# ATM90E3x-DB.net
KiCad netlist of a schematic drawn in Altium Designer
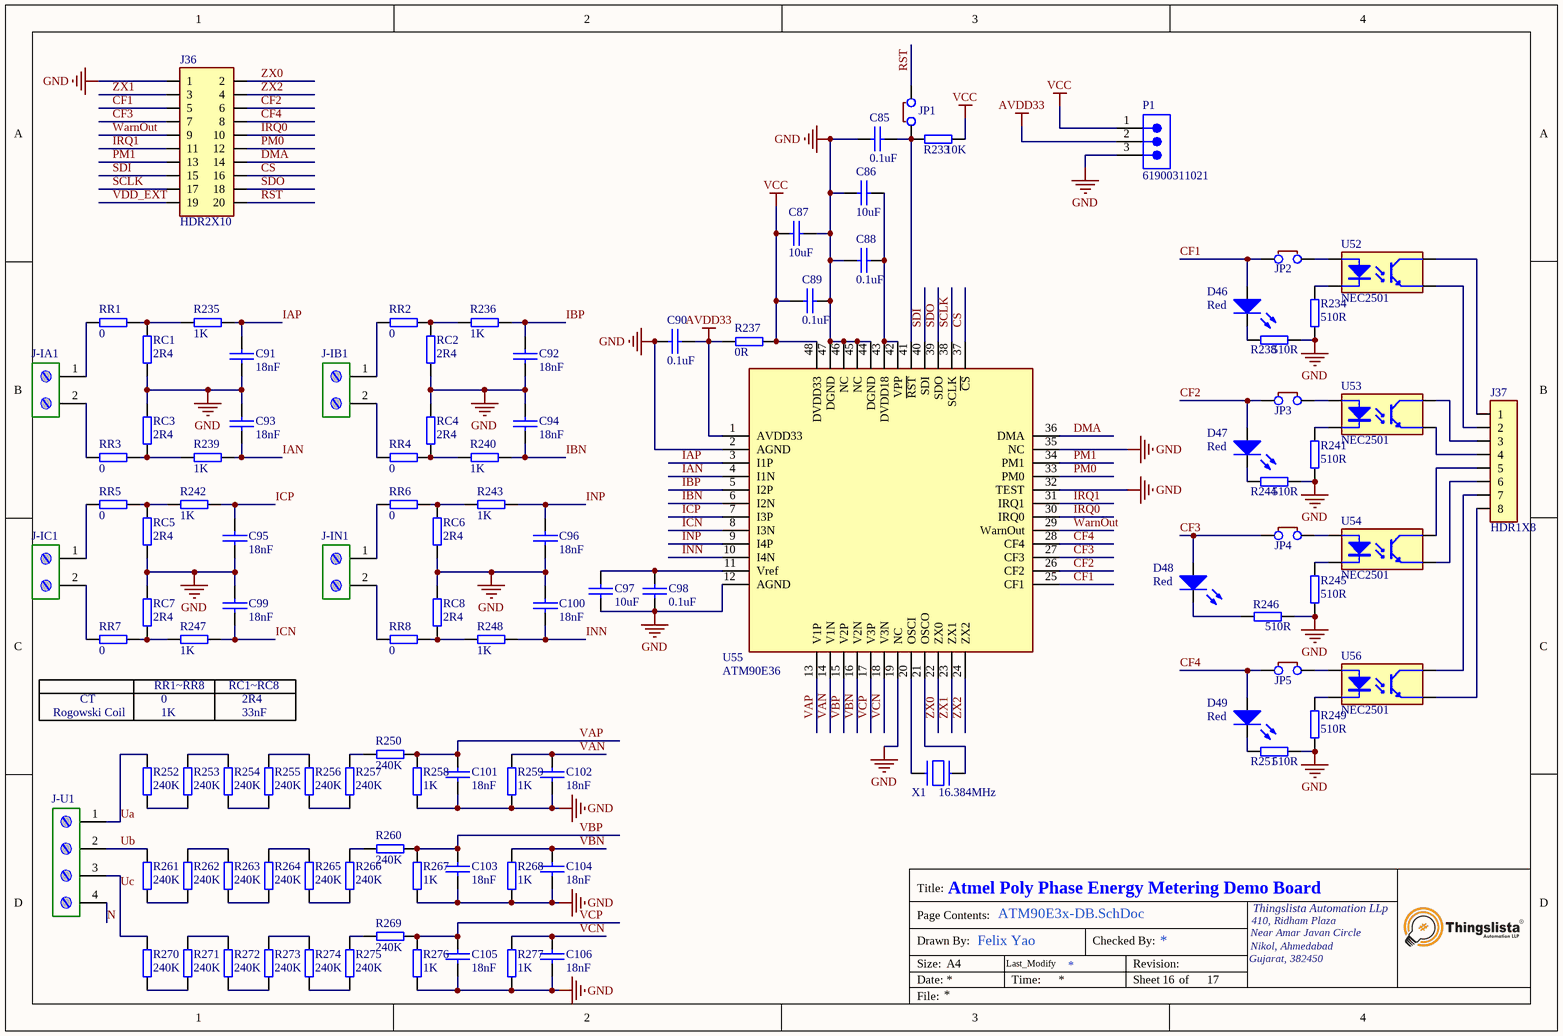
[diagram p0: ATM90E3x-DB.SchDoc]

(export (version "E")
  (design (tool "Eeschema 10.0.6"))
  (components
    (comp (ref "C85") (value "0.1uF") (footprint "C0603") (libsource (lib "SchLib(AD10)") (part "CAP")))
    (comp (ref "C86") (value "10uF") (footprint "C0805") (libsource (lib "SchLib(AD10)") (part "CAP")))
    (comp (ref "C87") (value "10uF") (footprint "C0805") (libsource (lib "SchLib(AD10)") (part "CAP")))
    (comp (ref "C88") (value "0.1uF") (footprint "C0603") (libsource (lib "SchLib(AD10)") (part "CAP")))
    (comp (ref "C89") (value "0.1uF") (footprint "C0603") (libsource (lib "SchLib(AD10)") (part "CAP")))
    (comp (ref "C90") (value "0.1uF") (footprint "C0603") (libsource (lib "SchLib(AD10)") (part "CAP")))
    (comp (ref "C91") (value "18nF") (footprint "C0805") (libsource (lib "SchLib(AD10)") (part "CAP")))
    (comp (ref "C92") (value "18nF") (footprint "C0805") (libsource (lib "SchLib(AD10)") (part "CAP")))
    (comp (ref "C93") (value "18nF") (footprint "C0805") (libsource (lib "SchLib(AD10)") (part "CAP")))
    (comp (ref "C94") (value "18nF") (footprint "C0805") (libsource (lib "SchLib(AD10)") (part "CAP")))
    (comp (ref "C95") (value "18nF") (footprint "C0805") (libsource (lib "SchLib(AD10)") (part "CAP")))
    (comp (ref "C96") (value "18nF") (footprint "C0805") (libsource (lib "SchLib(AD10)") (part "CAP")))
    (comp (ref "C97") (value "10uF") (footprint "C0805") (libsource (lib "SchLib(AD10)") (part "CAP")))
    (comp (ref "C98") (value "0.1uF") (footprint "C0603") (libsource (lib "SchLib(AD10)") (part "CAP")))
    (comp (ref "C99") (value "18nF") (footprint "C0805") (libsource (lib "SchLib(AD10)") (part "CAP")))
    (comp (ref "C100") (value "18nF") (footprint "C0805") (libsource (lib "SchLib(AD10)") (part "CAP")))
    (comp (ref "C101") (value "18nF") (footprint "C0805") (libsource (lib "SchLib(AD10)") (part "CAP")))
    (comp (ref "C102") (value "18nF") (footprint "C0805") (libsource (lib "SchLib(AD10)") (part "CAP")))
    (comp (ref "C103") (value "18nF") (footprint "C0805") (libsource (lib "SchLib(AD10)") (part "CAP")))
    (comp (ref "C104") (value "18nF") (footprint "C0805") (libsource (lib "SchLib(AD10)") (part "CAP")))
    (comp (ref "C105") (value "18nF") (footprint "C0805") (libsource (lib "SchLib(AD10)") (part "CAP")))
    (comp (ref "C106") (value "18nF") (footprint "C0805") (libsource (lib "SchLib(AD10)") (part "CAP")))
    (comp (ref "D46") (value "Red") (footprint "LED-0805R") (libsource (lib "SchLib(AD10)") (part "LED")))
    (comp (ref "D47") (value "Red") (footprint "LED-0805R") (libsource (lib "SchLib(AD10)") (part "LED")))
    (comp (ref "D48") (value "Red") (footprint "LED-0805R") (libsource (lib "SchLib(AD10)") (part "LED")))
    (comp (ref "D49") (value "Red") (footprint "LED-0805R") (libsource (lib "SchLib(AD10)") (part "LED")))
    (comp (ref "J-IA1")
      (value "~")
      (footprint "TE-1776119-2")
      (libsource (lib "SchLib(AD10)") (part "Terminal-Screw-2"))
    )
    (comp (ref "J-IB1")
      (value "~")
      (footprint "TE-1776119-2")
      (libsource (lib "SchLib(AD10)") (part "Terminal-Screw-2"))
    )
    (comp (ref "J-IC1")
      (value "~")
      (footprint "TE-1776119-2")
      (libsource (lib "SchLib(AD10)") (part "Terminal-Screw-2"))
    )
    (comp (ref "J-IN1")
      (value "~")
      (footprint "TE-1776119-2")
      (libsource (lib "SchLib(AD10)") (part "Terminal-Screw-2"))
    )
    (comp (ref "J-U1")
      (value "~")
      (footprint "TE-282843-4")
      (libsource (lib "SchLib(AD10)") (part "Terminal-Screw-4"))
    )
    (comp (ref "J36")
      (value "HDR2X10")
      (footprint "HDR2X10")
      (libsource (lib "SchLib(AD10)") (part "HDR2X10"))
    )
    (comp (ref "J37") (value "HDR1X8") (footprint "HDR1X8") (libsource (lib "SchLib(AD10)") (part "HDR1X8")))
    (comp (ref "JP1") (value "JMP") (footprint "JMP") (libsource (lib "SchLib(AD10)") (part "JMP")))
    (comp (ref "JP2") (value "JMP") (footprint "JMP") (libsource (lib "SchLib(AD10)") (part "JMP")))
    (comp (ref "JP3") (value "JMP") (footprint "JMP") (libsource (lib "SchLib(AD10)") (part "JMP")))
    (comp (ref "JP4") (value "JMP") (footprint "JMP") (libsource (lib "SchLib(AD10)") (part "JMP")))
    (comp (ref "JP5") (value "JMP") (footprint "JMP") (libsource (lib "SchLib(AD10)") (part "JMP")))
    (comp (ref "P1")
      (value "61900311021")
      (footprint "61900311021")
      (libsource (lib "Altium Content Vault") (part "Header_Male_1R_03P"))
    )
    (comp (ref "R233") (value "10K") (footprint "R0603") (libsource (lib "SchLib(AD10)") (part "RES")))
    (comp (ref "R234") (value "510R") (footprint "R0805") (libsource (lib "SchLib(AD10)") (part "RES")))
    (comp (ref "R235") (value "1K") (footprint "R0805") (libsource (lib "SchLib(AD10)") (part "RES")))
    (comp (ref "R236") (value "1K") (footprint "R0805") (libsource (lib "SchLib(AD10)") (part "RES")))
    (comp (ref "R237") (value "0R") (footprint "R0603") (libsource (lib "SchLib(AD10)") (part "RES")))
    (comp (ref "R238") (value "510R") (footprint "R0805") (libsource (lib "SchLib(AD10)") (part "RES")))
    (comp (ref "R239") (value "1K") (footprint "R0805") (libsource (lib "SchLib(AD10)") (part "RES")))
    (comp (ref "R240") (value "1K") (footprint "R0805") (libsource (lib "SchLib(AD10)") (part "RES")))
    (comp (ref "R241") (value "510R") (footprint "R0805") (libsource (lib "SchLib(AD10)") (part "RES")))
    (comp (ref "R242") (value "1K") (footprint "R0805") (libsource (lib "SchLib(AD10)") (part "RES")))
    (comp (ref "R243") (value "1K") (footprint "R0805") (libsource (lib "SchLib(AD10)") (part "RES")))
    (comp (ref "R244") (value "510R") (footprint "R0805") (libsource (lib "SchLib(AD10)") (part "RES")))
    (comp (ref "R245") (value "510R") (footprint "R0805") (libsource (lib "SchLib(AD10)") (part "RES")))
    (comp (ref "R246") (value "510R") (footprint "R0805") (libsource (lib "SchLib(AD10)") (part "RES")))
    (comp (ref "R247") (value "1K") (footprint "R0805") (libsource (lib "SchLib(AD10)") (part "RES")))
    (comp (ref "R248") (value "1K") (footprint "R0805") (libsource (lib "SchLib(AD10)") (part "RES")))
    (comp (ref "R249") (value "510R") (footprint "R0805") (libsource (lib "SchLib(AD10)") (part "RES")))
    (comp (ref "R250") (value "240K") (footprint "R1206") (libsource (lib "SchLib(AD10)") (part "RES")))
    (comp (ref "R251") (value "510R") (footprint "R0805") (libsource (lib "SchLib(AD10)") (part "RES")))
    (comp (ref "R252") (value "240K") (footprint "R1206") (libsource (lib "SchLib(AD10)") (part "RES")))
    (comp (ref "R253") (value "240K") (footprint "R1206") (libsource (lib "SchLib(AD10)") (part "RES")))
    (comp (ref "R254") (value "240K") (footprint "R1206") (libsource (lib "SchLib(AD10)") (part "RES")))
    (comp (ref "R255") (value "240K") (footprint "R1206") (libsource (lib "SchLib(AD10)") (part "RES")))
    (comp (ref "R256") (value "240K") (footprint "R1206") (libsource (lib "SchLib(AD10)") (part "RES")))
    (comp (ref "R257") (value "240K") (footprint "R1206") (libsource (lib "SchLib(AD10)") (part "RES")))
    (comp (ref "R258") (value "1K") (footprint "R0805") (libsource (lib "SchLib(AD10)") (part "RES")))
    (comp (ref "R259") (value "1K") (footprint "R0805") (libsource (lib "SchLib(AD10)") (part "RES")))
    (comp (ref "R260") (value "240K") (footprint "R1206") (libsource (lib "SchLib(AD10)") (part "RES")))
    (comp (ref "R261") (value "240K") (footprint "R1206") (libsource (lib "SchLib(AD10)") (part "RES")))
    (comp (ref "R262") (value "240K") (footprint "R1206") (libsource (lib "SchLib(AD10)") (part "RES")))
    (comp (ref "R263") (value "240K") (footprint "R1206") (libsource (lib "SchLib(AD10)") (part "RES")))
    (comp (ref "R264") (value "240K") (footprint "R1206") (libsource (lib "SchLib(AD10)") (part "RES")))
    (comp (ref "R265") (value "240K") (footprint "R1206") (libsource (lib "SchLib(AD10)") (part "RES")))
    (comp (ref "R266") (value "240K") (footprint "R1206") (libsource (lib "SchLib(AD10)") (part "RES")))
    (comp (ref "R267") (value "1K") (footprint "R0805") (libsource (lib "SchLib(AD10)") (part "RES")))
    (comp (ref "R268") (value "1K") (footprint "R0805") (libsource (lib "SchLib(AD10)") (part "RES")))
    (comp (ref "R269") (value "240K") (footprint "R1206") (libsource (lib "SchLib(AD10)") (part "RES")))
    (comp (ref "R270") (value "240K") (footprint "R1206") (libsource (lib "SchLib(AD10)") (part "RES")))
    (comp (ref "R271") (value "240K") (footprint "R1206") (libsource (lib "SchLib(AD10)") (part "RES")))
    (comp (ref "R272") (value "240K") (footprint "R1206") (libsource (lib "SchLib(AD10)") (part "RES")))
    (comp (ref "R273") (value "240K") (footprint "R1206") (libsource (lib "SchLib(AD10)") (part "RES")))
    (comp (ref "R274") (value "240K") (footprint "R1206") (libsource (lib "SchLib(AD10)") (part "RES")))
    (comp (ref "R275") (value "240K") (footprint "R1206") (libsource (lib "SchLib(AD10)") (part "RES")))
    (comp (ref "R276") (value "1K") (footprint "R0805") (libsource (lib "SchLib(AD10)") (part "RES")))
    (comp (ref "R277") (value "1K") (footprint "R0805") (libsource (lib "SchLib(AD10)") (part "RES")))
    (comp (ref "RC1") (value "2R4") (footprint "R0805") (libsource (lib "SchLib(AD10)") (part "RES")))
    (comp (ref "RC2") (value "2R4") (footprint "R0805") (libsource (lib "SchLib(AD10)") (part "RES")))
    (comp (ref "RC3") (value "2R4") (footprint "R0805") (libsource (lib "SchLib(AD10)") (part "RES")))
    (comp (ref "RC4") (value "2R4") (footprint "R0805") (libsource (lib "SchLib(AD10)") (part "RES")))
    (comp (ref "RC5") (value "2R4") (footprint "R0805") (libsource (lib "SchLib(AD10)") (part "RES")))
    (comp (ref "RC6") (value "2R4") (footprint "R0805") (libsource (lib "SchLib(AD10)") (part "RES")))
    (comp (ref "RC7") (value "2R4") (footprint "R0805") (libsource (lib "SchLib(AD10)") (part "RES")))
    (comp (ref "RC8") (value "2R4") (footprint "R0805") (libsource (lib "SchLib(AD10)") (part "RES")))
    (comp (ref "RR1") (value "0") (footprint "R0805") (libsource (lib "SchLib(AD10)") (part "RES")))
    (comp (ref "RR2") (value "0") (footprint "R0805") (libsource (lib "SchLib(AD10)") (part "RES")))
    (comp (ref "RR3") (value "0") (footprint "R0805") (libsource (lib "SchLib(AD10)") (part "RES")))
    (comp (ref "RR4") (value "0") (footprint "R0805") (libsource (lib "SchLib(AD10)") (part "RES")))
    (comp (ref "RR5") (value "0") (footprint "R0805") (libsource (lib "SchLib(AD10)") (part "RES")))
    (comp (ref "RR6") (value "0") (footprint "R0805") (libsource (lib "SchLib(AD10)") (part "RES")))
    (comp (ref "RR7") (value "0") (footprint "R0805") (libsource (lib "SchLib(AD10)") (part "RES")))
    (comp (ref "RR8") (value "0") (footprint "R0805") (libsource (lib "SchLib(AD10)") (part "RES")))
    (comp (ref "U52")
      (value "NEC2501")
      (footprint "PS2501L-1")
      (libsource (lib "SchLib(AD10)") (part "NEC2501"))
    )
    (comp (ref "U53")
      (value "NEC2501")
      (footprint "PS2501L-1")
      (libsource (lib "SchLib(AD10)") (part "NEC2501"))
    )
    (comp (ref "U54")
      (value "NEC2501")
      (footprint "PS2501L-1")
      (libsource (lib "SchLib(AD10)") (part "NEC2501"))
    )
    (comp (ref "U55")
      (value "ATM90E36")
      (footprint "TQFP-48(7x7)")
      (description "ATM90E3X")
      (libsource (lib "SchLib(AD10)") (part "ATM90E3X"))
    )
    (comp (ref "U56")
      (value "NEC2501")
      (footprint "PS2501L-1")
      (libsource (lib "SchLib(AD10)") (part "NEC2501"))
    )
    (comp (ref "X1")
      (value "16.384MHz")
      (footprint "XTAL-MIX-49")
      (libsource (lib "SchLib(AD10)") (part "XTAL-T"))
    )
  )
  (nets
    (net (code "1") (name "/CF1") (class "Default")
      (node (ref "D46") (pin "A") (pinfunction "A_A") (pintype "passive"))
      (node (ref "J36") (pin "5") (pinfunction "5_5") (pintype "passive"))
      (node (ref "JP2") (pin "1") (pinfunction "1_1") (pintype "passive"))
      (node (ref "U55") (pin "25") (pinfunction "CF1_25") (pintype "passive"))
    )
    (net (code "2") (name "/CF2") (class "Default")
      (node (ref "D47") (pin "A") (pinfunction "A_A") (pintype "passive"))
      (node (ref "J36") (pin "6") (pinfunction "6_6") (pintype "passive"))
      (node (ref "JP3") (pin "1") (pinfunction "1_1") (pintype "passive"))
      (node (ref "U55") (pin "26") (pinfunction "CF2_26") (pintype "passive"))
    )
    (net (code "3") (name "/CF3") (class "Default")
      (node (ref "D48") (pin "A") (pinfunction "A_A") (pintype "passive"))
      (node (ref "J36") (pin "7") (pinfunction "7_7") (pintype "passive"))
      (node (ref "JP4") (pin "1") (pinfunction "1_1") (pintype "passive"))
      (node (ref "U55") (pin "27") (pinfunction "CF3_27") (pintype "passive"))
    )
    (net (code "4") (name "/CF4") (class "Default")
      (node (ref "D49") (pin "A") (pinfunction "A_A") (pintype "passive"))
      (node (ref "J36") (pin "8") (pinfunction "8_8") (pintype "passive"))
      (node (ref "JP5") (pin "1") (pinfunction "1_1") (pintype "passive"))
      (node (ref "U55") (pin "28") (pinfunction "CF4_28") (pintype "passive"))
    )
    (net (code "5") (name "/CS") (class "Default")
      (node (ref "J36") (pin "16") (pinfunction "16_16") (pintype "passive"))
      (node (ref "U55") (pin "37") (pinfunction "~{CS}_37") (pintype "passive"))
    )
    (net (code "6") (name "/DMA") (class "Default")
      (node (ref "J36") (pin "14") (pinfunction "14_14") (pintype "passive"))
      (node (ref "U55") (pin "36") (pinfunction "DMA_36") (pintype "passive"))
    )
    (net (code "7") (name "/IAN") (class "Default")
      (node (ref "C93") (pin "1") (pintype "passive"))
      (node (ref "R239") (pin "1") (pinfunction "1_1") (pintype "passive"))
      (node (ref "U55") (pin "4") (pinfunction "I1N_4") (pintype "passive"))
    )
    (net (code "8") (name "/IAP") (class "Default")
      (node (ref "C91") (pin "2") (pintype "passive"))
      (node (ref "R235") (pin "1") (pinfunction "1_1") (pintype "passive"))
      (node (ref "U55") (pin "3") (pinfunction "I1P_3") (pintype "passive"))
    )
    (net (code "9") (name "/IBN") (class "Default")
      (node (ref "C94") (pin "2") (pintype "passive"))
      (node (ref "R240") (pin "2") (pinfunction "2_2") (pintype "passive"))
      (node (ref "U55") (pin "6") (pinfunction "I2N_6") (pintype "passive"))
    )
    (net (code "10") (name "/IBP") (class "Default")
      (node (ref "C92") (pin "1") (pintype "passive"))
      (node (ref "R236") (pin "2") (pinfunction "2_2") (pintype "passive"))
      (node (ref "U55") (pin "5") (pinfunction "I2P_5") (pintype "passive"))
    )
    (net (code "11") (name "/ICN") (class "Default")
      (node (ref "C99") (pin "2") (pintype "passive"))
      (node (ref "R247") (pin "2") (pinfunction "2_2") (pintype "passive"))
      (node (ref "U55") (pin "8") (pinfunction "I3N_8") (pintype "passive"))
    )
    (net (code "12") (name "/ICP") (class "Default")
      (node (ref "C95") (pin "1") (pintype "passive"))
      (node (ref "R242") (pin "2") (pinfunction "2_2") (pintype "passive"))
      (node (ref "U55") (pin "7") (pinfunction "I3P_7") (pintype "passive"))
    )
    (net (code "13") (name "/INN") (class "Default")
      (node (ref "C100") (pin "2") (pintype "passive"))
      (node (ref "R248") (pin "2") (pinfunction "2_2") (pintype "passive"))
      (node (ref "U55") (pin "10") (pinfunction "I4N_10") (pintype "passive"))
    )
    (net (code "14") (name "/INP") (class "Default")
      (node (ref "C96") (pin "1") (pintype "passive"))
      (node (ref "R243") (pin "2") (pinfunction "2_2") (pintype "passive"))
      (node (ref "U55") (pin "9") (pinfunction "I4P_9") (pintype "passive"))
    )
    (net (code "15") (name "/IRQ0") (class "Default")
      (node (ref "J36") (pin "10") (pinfunction "10_10") (pintype "passive"))
      (node (ref "U55") (pin "30") (pinfunction "IRQ0_30") (pintype "passive"))
    )
    (net (code "16") (name "/IRQ1") (class "Default")
      (node (ref "J36") (pin "11") (pinfunction "11_11") (pintype "passive"))
      (node (ref "U55") (pin "31") (pinfunction "IRQ1_31") (pintype "passive"))
    )
    (net (code "17") (name "/N") (class "Default")
      (node (ref "J-U1") (pin "4") (pinfunction "4_4") (pintype "passive"))
    )
    (net (code "18") (name "/PM0") (class "Default")
      (node (ref "J36") (pin "12") (pinfunction "12_12") (pintype "passive"))
      (node (ref "U55") (pin "33") (pinfunction "PM0_33") (pintype "passive"))
    )
    (net (code "19") (name "/PM1") (class "Default")
      (node (ref "J36") (pin "13") (pinfunction "13_13") (pintype "passive"))
      (node (ref "U55") (pin "34") (pinfunction "PM1_34") (pintype "passive"))
    )
    (net (code "20") (name "/RST") (class "Default")
      (node (ref "J36") (pin "20") (pinfunction "20_20") (pintype "passive"))
      (node (ref "JP1") (pin "2") (pinfunction "2_2") (pintype "passive"))
    )
    (net (code "21") (name "/SCLK") (class "Default")
      (node (ref "J36") (pin "17") (pinfunction "17_17") (pintype "passive"))
      (node (ref "U55") (pin "38") (pinfunction "SCLK_38") (pintype "passive"))
    )
    (net (code "22") (name "/SDI") (class "Default")
      (node (ref "J36") (pin "15") (pinfunction "15_15") (pintype "passive"))
      (node (ref "U55") (pin "40") (pinfunction "SDI_40") (pintype "passive"))
    )
    (net (code "23") (name "/SDO") (class "Default")
      (node (ref "J36") (pin "18") (pinfunction "18_18") (pintype "passive"))
      (node (ref "U55") (pin "39") (pinfunction "SDO_39") (pintype "passive"))
    )
    (net (code "24") (name "/Ua") (class "Default")
      (node (ref "J-U1") (pin "1") (pinfunction "1_1") (pintype "passive"))
      (node (ref "R252") (pin "1") (pinfunction "1_1") (pintype "passive"))
    )
    (net (code "25") (name "/Ub") (class "Default")
      (node (ref "J-U1") (pin "2") (pinfunction "2_2") (pintype "passive"))
      (node (ref "R261") (pin "2") (pinfunction "2_2") (pintype "passive"))
    )
    (net (code "26") (name "/Uc") (class "Default")
      (node (ref "J-U1") (pin "3") (pinfunction "3_3") (pintype "passive"))
      (node (ref "R270") (pin "2") (pinfunction "2_2") (pintype "passive"))
    )
    (net (code "27") (name "/VAN") (class "Default")
      (node (ref "C102") (pin "2") (pintype "passive"))
      (node (ref "R259") (pin "2") (pinfunction "2_2") (pintype "passive"))
      (node (ref "U55") (pin "14") (pinfunction "V1N_14") (pintype "passive"))
    )
    (net (code "28") (name "/VAP") (class "Default")
      (node (ref "C101") (pin "2") (pintype "passive"))
      (node (ref "R250") (pin "2") (pinfunction "2_2") (pintype "passive"))
      (node (ref "R258") (pin "2") (pinfunction "2_2") (pintype "passive"))
      (node (ref "U55") (pin "13") (pinfunction "V1P_13") (pintype "passive"))
    )
    (net (code "29") (name "/VBN") (class "Default")
      (node (ref "C104") (pin "2") (pintype "passive"))
      (node (ref "R268") (pin "2") (pinfunction "2_2") (pintype "passive"))
      (node (ref "U55") (pin "16") (pinfunction "V2N_16") (pintype "passive"))
    )
    (net (code "30") (name "/VBP") (class "Default")
      (node (ref "C103") (pin "2") (pintype "passive"))
      (node (ref "R260") (pin "1") (pinfunction "1_1") (pintype "passive"))
      (node (ref "R267") (pin "2") (pinfunction "2_2") (pintype "passive"))
      (node (ref "U55") (pin "15") (pinfunction "V2P_15") (pintype "passive"))
    )
    (net (code "31") (name "/VCN") (class "Default")
      (node (ref "C106") (pin "2") (pintype "passive"))
      (node (ref "R277") (pin "2") (pinfunction "2_2") (pintype "passive"))
      (node (ref "U55") (pin "18") (pinfunction "V3N_18") (pintype "passive"))
    )
    (net (code "32") (name "/VCP") (class "Default")
      (node (ref "C105") (pin "2") (pintype "passive"))
      (node (ref "R269") (pin "1") (pinfunction "1_1") (pintype "passive"))
      (node (ref "R276") (pin "2") (pinfunction "2_2") (pintype "passive"))
      (node (ref "U55") (pin "17") (pinfunction "V3P_17") (pintype "passive"))
    )
    (net (code "33") (name "/VDD_EXT") (class "Default")
      (node (ref "J36") (pin "19") (pinfunction "19_19") (pintype "passive"))
    )
    (net (code "34") (name "/WarnOut") (class "Default")
      (node (ref "J36") (pin "9") (pinfunction "9_9") (pintype "passive"))
      (node (ref "U55") (pin "29") (pinfunction "WarnOut_29") (pintype "passive"))
    )
    (net (code "35") (name "/ZX0") (class "Default")
      (node (ref "J36") (pin "2") (pinfunction "2_2") (pintype "passive"))
      (node (ref "U55") (pin "22") (pinfunction "ZX0_22") (pintype "passive"))
    )
    (net (code "36") (name "/ZX1") (class "Default")
      (node (ref "J36") (pin "3") (pinfunction "3_3") (pintype "passive"))
      (node (ref "U55") (pin "23") (pinfunction "ZX1_23") (pintype "passive"))
    )
    (net (code "37") (name "/ZX2") (class "Default")
      (node (ref "J36") (pin "4") (pinfunction "4_4") (pintype "passive"))
      (node (ref "U55") (pin "24") (pinfunction "ZX2_24") (pintype "passive"))
    )
    (net (code "38") (name "AVDD33") (class "Default")
      (node (ref "C90") (pin "2") (pintype "passive"))
      (node (ref "P1") (pin "2") (pinfunction "2_2") (pintype "passive"))
      (node (ref "R237") (pin "2") (pinfunction "2_2") (pintype "passive"))
      (node (ref "U55") (pin "1") (pinfunction "AVDD33_1") (pintype "passive"))
    )
    (net (code "39") (name "GND") (class "Default")
      (node (ref "C100") (pin "1") (pintype "passive"))
      (node (ref "C101") (pin "1") (pintype "passive"))
      (node (ref "C102") (pin "1") (pintype "passive"))
      (node (ref "C103") (pin "1") (pintype "passive"))
      (node (ref "C104") (pin "1") (pintype "passive"))
      (node (ref "C105") (pin "1") (pintype "passive"))
      (node (ref "C106") (pin "1") (pintype "passive"))
      (node (ref "C85") (pin "1") (pintype "passive"))
      (node (ref "C86") (pin "2") (pintype "passive"))
      (node (ref "C87") (pin "1") (pintype "passive"))
      (node (ref "C88") (pin "1") (pintype "passive"))
      (node (ref "C89") (pin "2") (pintype "passive"))
      (node (ref "C90") (pin "1") (pintype "passive"))
      (node (ref "C91") (pin "1") (pintype "passive"))
      (node (ref "C92") (pin "2") (pintype "passive"))
      (node (ref "C93") (pin "2") (pintype "passive"))
      (node (ref "C94") (pin "1") (pintype "passive"))
      (node (ref "C95") (pin "2") (pintype "passive"))
      (node (ref "C96") (pin "2") (pintype "passive"))
      (node (ref "C97") (pin "1") (pintype "passive"))
      (node (ref "C98") (pin "1") (pintype "passive"))
      (node (ref "C99") (pin "1") (pintype "passive"))
      (node (ref "J36") (pin "1") (pinfunction "1_1") (pintype "passive"))
      (node (ref "P1") (pin "3") (pinfunction "3_3") (pintype "passive"))
      (node (ref "R234") (pin "1") (pinfunction "1_1") (pintype "passive"))
      (node (ref "R238") (pin "1") (pinfunction "1_1") (pintype "passive"))
      (node (ref "R241") (pin "1") (pinfunction "1_1") (pintype "passive"))
      (node (ref "R244") (pin "1") (pinfunction "1_1") (pintype "passive"))
      (node (ref "R245") (pin "1") (pinfunction "1_1") (pintype "passive"))
      (node (ref "R246") (pin "1") (pinfunction "1_1") (pintype "passive"))
      (node (ref "R249") (pin "1") (pinfunction "1_1") (pintype "passive"))
      (node (ref "R251") (pin "1") (pinfunction "1_1") (pintype "passive"))
      (node (ref "R258") (pin "1") (pinfunction "1_1") (pintype "passive"))
      (node (ref "R259") (pin "1") (pinfunction "1_1") (pintype "passive"))
      (node (ref "R267") (pin "1") (pinfunction "1_1") (pintype "passive"))
      (node (ref "R268") (pin "1") (pinfunction "1_1") (pintype "passive"))
      (node (ref "R276") (pin "1") (pinfunction "1_1") (pintype "passive"))
      (node (ref "R277") (pin "1") (pinfunction "1_1") (pintype "passive"))
      (node (ref "RC1") (pin "1") (pinfunction "1_1") (pintype "passive"))
      (node (ref "RC2") (pin "1") (pinfunction "1_1") (pintype "passive"))
      (node (ref "RC3") (pin "2") (pinfunction "2_2") (pintype "passive"))
      (node (ref "RC4") (pin "2") (pinfunction "2_2") (pintype "passive"))
      (node (ref "RC5") (pin "1") (pinfunction "1_1") (pintype "passive"))
      (node (ref "RC6") (pin "1") (pinfunction "1_1") (pintype "passive"))
      (node (ref "RC7") (pin "2") (pinfunction "2_2") (pintype "passive"))
      (node (ref "RC8") (pin "2") (pinfunction "2_2") (pintype "passive"))
      (node (ref "U55") (pin "12") (pinfunction "AGND_12") (pintype "passive"))
      (node (ref "U55") (pin "19") (pinfunction "NC_19") (pintype "passive"))
      (node (ref "U55") (pin "2") (pinfunction "AGND_2") (pintype "passive"))
      (node (ref "U55") (pin "32") (pinfunction "TEST_32") (pintype "passive"))
      (node (ref "U55") (pin "35") (pinfunction "NC_35") (pintype "passive"))
      (node (ref "U55") (pin "44") (pinfunction "DGND_44") (pintype "passive"))
      (node (ref "U55") (pin "45") (pinfunction "NC_45") (pintype "passive"))
      (node (ref "U55") (pin "46") (pinfunction "NC_46") (pintype "passive"))
      (node (ref "U55") (pin "47") (pinfunction "DGND_47") (pintype "passive"))
    )
    (net (code "40") (name "Net-(D46-PadK)") (class "Default")
      (node (ref "D46") (pin "K") (pinfunction "K_K") (pintype "passive"))
      (node (ref "R238") (pin "2") (pinfunction "2_2") (pintype "passive"))
    )
    (net (code "41") (name "Net-(D47-PadK)") (class "Default")
      (node (ref "D47") (pin "K") (pinfunction "K_K") (pintype "passive"))
      (node (ref "R244") (pin "2") (pinfunction "2_2") (pintype "passive"))
    )
    (net (code "42") (name "Net-(D48-PadK)") (class "Default")
      (node (ref "D48") (pin "K") (pinfunction "K_K") (pintype "passive"))
      (node (ref "R246") (pin "2") (pinfunction "2_2") (pintype "passive"))
    )
    (net (code "43") (name "Net-(D49-PadK)") (class "Default")
      (node (ref "D49") (pin "K") (pinfunction "K_K") (pintype "passive"))
      (node (ref "R251") (pin "2") (pinfunction "2_2") (pintype "passive"))
    )
    (net (code "44") (name "Net-(J-IA1-Pad1)") (class "Default")
      (node (ref "J-IA1") (pin "1") (pinfunction "1_1") (pintype "passive"))
      (node (ref "RR1") (pin "2") (pinfunction "2_2") (pintype "passive"))
    )
    (net (code "45") (name "Net-(J-IA1-Pad2)") (class "Default")
      (node (ref "J-IA1") (pin "2") (pinfunction "2_2") (pintype "passive"))
      (node (ref "RR3") (pin "2") (pinfunction "2_2") (pintype "passive"))
    )
    (net (code "46") (name "Net-(J-IB1-Pad1)") (class "Default")
      (node (ref "J-IB1") (pin "1") (pinfunction "1_1") (pintype "passive"))
      (node (ref "RR2") (pin "2") (pinfunction "2_2") (pintype "passive"))
    )
    (net (code "47") (name "Net-(J-IB1-Pad2)") (class "Default")
      (node (ref "J-IB1") (pin "2") (pinfunction "2_2") (pintype "passive"))
      (node (ref "RR4") (pin "2") (pinfunction "2_2") (pintype "passive"))
    )
    (net (code "48") (name "Net-(J-IC1-Pad1)") (class "Default")
      (node (ref "J-IC1") (pin "1") (pinfunction "1_1") (pintype "passive"))
      (node (ref "RR5") (pin "2") (pinfunction "2_2") (pintype "passive"))
    )
    (net (code "49") (name "Net-(J-IC1-Pad2)") (class "Default")
      (node (ref "J-IC1") (pin "2") (pinfunction "2_2") (pintype "passive"))
      (node (ref "RR7") (pin "2") (pinfunction "2_2") (pintype "passive"))
    )
    (net (code "50") (name "Net-(J-IN1-Pad1)") (class "Default")
      (node (ref "J-IN1") (pin "1") (pinfunction "1_1") (pintype "passive"))
      (node (ref "RR6") (pin "2") (pinfunction "2_2") (pintype "passive"))
    )
    (net (code "51") (name "Net-(J-IN1-Pad2)") (class "Default")
      (node (ref "J-IN1") (pin "2") (pinfunction "2_2") (pintype "passive"))
      (node (ref "RR8") (pin "2") (pinfunction "2_2") (pintype "passive"))
    )
    (net (code "52") (name "Net-(R235-Pad2)") (class "Default")
      (node (ref "R235") (pin "2") (pinfunction "2_2") (pintype "passive"))
      (node (ref "RC1") (pin "2") (pinfunction "2_2") (pintype "passive"))
      (node (ref "RR1") (pin "1") (pinfunction "1_1") (pintype "passive"))
    )
    (net (code "53") (name "Net-(R236-Pad1)") (class "Default")
      (node (ref "R236") (pin "1") (pinfunction "1_1") (pintype "passive"))
      (node (ref "RC2") (pin "2") (pinfunction "2_2") (pintype "passive"))
      (node (ref "RR2") (pin "1") (pinfunction "1_1") (pintype "passive"))
    )
    (net (code "54") (name "Net-(R239-Pad2)") (class "Default")
      (node (ref "R239") (pin "2") (pinfunction "2_2") (pintype "passive"))
      (node (ref "RC3") (pin "1") (pinfunction "1_1") (pintype "passive"))
      (node (ref "RR3") (pin "1") (pinfunction "1_1") (pintype "passive"))
    )
    (net (code "55") (name "Net-(R240-Pad1)") (class "Default")
      (node (ref "R240") (pin "1") (pinfunction "1_1") (pintype "passive"))
      (node (ref "RC4") (pin "1") (pinfunction "1_1") (pintype "passive"))
      (node (ref "RR4") (pin "1") (pinfunction "1_1") (pintype "passive"))
    )
    (net (code "56") (name "Net-(R242-Pad1)") (class "Default")
      (node (ref "R242") (pin "1") (pinfunction "1_1") (pintype "passive"))
      (node (ref "RC5") (pin "2") (pinfunction "2_2") (pintype "passive"))
      (node (ref "RR5") (pin "1") (pinfunction "1_1") (pintype "passive"))
    )
    (net (code "57") (name "Net-(R243-Pad1)") (class "Default")
      (node (ref "R243") (pin "1") (pinfunction "1_1") (pintype "passive"))
      (node (ref "RC6") (pin "2") (pinfunction "2_2") (pintype "passive"))
      (node (ref "RR6") (pin "1") (pinfunction "1_1") (pintype "passive"))
    )
    (net (code "58") (name "Net-(R247-Pad1)") (class "Default")
      (node (ref "R247") (pin "1") (pinfunction "1_1") (pintype "passive"))
      (node (ref "RC7") (pin "1") (pinfunction "1_1") (pintype "passive"))
      (node (ref "RR7") (pin "1") (pinfunction "1_1") (pintype "passive"))
    )
    (net (code "59") (name "Net-(R248-Pad1)") (class "Default")
      (node (ref "R248") (pin "1") (pinfunction "1_1") (pintype "passive"))
      (node (ref "RC8") (pin "1") (pinfunction "1_1") (pintype "passive"))
      (node (ref "RR8") (pin "1") (pinfunction "1_1") (pintype "passive"))
    )
    (net (code "60") (name "Net-(R250-Pad1)") (class "Default")
      (node (ref "R250") (pin "1") (pinfunction "1_1") (pintype "passive"))
      (node (ref "R257") (pin "1") (pinfunction "1_1") (pintype "passive"))
    )
    (net (code "61") (name "Net-(R252-Pad2)") (class "Default")
      (node (ref "R252") (pin "2") (pinfunction "2_2") (pintype "passive"))
      (node (ref "R253") (pin "2") (pinfunction "2_2") (pintype "passive"))
    )
    (net (code "62") (name "Net-(R253-Pad1)") (class "Default")
      (node (ref "R253") (pin "1") (pinfunction "1_1") (pintype "passive"))
      (node (ref "R254") (pin "1") (pinfunction "1_1") (pintype "passive"))
    )
    (net (code "63") (name "Net-(R254-Pad2)") (class "Default")
      (node (ref "R254") (pin "2") (pinfunction "2_2") (pintype "passive"))
      (node (ref "R255") (pin "2") (pinfunction "2_2") (pintype "passive"))
    )
    (net (code "64") (name "Net-(R255-Pad1)") (class "Default")
      (node (ref "R255") (pin "1") (pinfunction "1_1") (pintype "passive"))
      (node (ref "R256") (pin "1") (pinfunction "1_1") (pintype "passive"))
    )
    (net (code "65") (name "Net-(R256-Pad2)") (class "Default")
      (node (ref "R256") (pin "2") (pinfunction "2_2") (pintype "passive"))
      (node (ref "R257") (pin "2") (pinfunction "2_2") (pintype "passive"))
    )
    (net (code "66") (name "Net-(R260-Pad2)") (class "Default")
      (node (ref "R260") (pin "2") (pinfunction "2_2") (pintype "passive"))
      (node (ref "R266") (pin "2") (pinfunction "2_2") (pintype "passive"))
    )
    (net (code "67") (name "Net-(R261-Pad1)") (class "Default")
      (node (ref "R261") (pin "1") (pinfunction "1_1") (pintype "passive"))
      (node (ref "R262") (pin "1") (pinfunction "1_1") (pintype "passive"))
    )
    (net (code "68") (name "Net-(R262-Pad2)") (class "Default")
      (node (ref "R262") (pin "2") (pinfunction "2_2") (pintype "passive"))
      (node (ref "R263") (pin "2") (pinfunction "2_2") (pintype "passive"))
    )
    (net (code "69") (name "Net-(R263-Pad1)") (class "Default")
      (node (ref "R263") (pin "1") (pinfunction "1_1") (pintype "passive"))
      (node (ref "R264") (pin "1") (pinfunction "1_1") (pintype "passive"))
    )
    (net (code "70") (name "Net-(R264-Pad2)") (class "Default")
      (node (ref "R264") (pin "2") (pinfunction "2_2") (pintype "passive"))
      (node (ref "R265") (pin "2") (pinfunction "2_2") (pintype "passive"))
    )
    (net (code "71") (name "Net-(R265-Pad1)") (class "Default")
      (node (ref "R265") (pin "1") (pinfunction "1_1") (pintype "passive"))
      (node (ref "R266") (pin "1") (pinfunction "1_1") (pintype "passive"))
    )
    (net (code "72") (name "Net-(R269-Pad2)") (class "Default")
      (node (ref "R269") (pin "2") (pinfunction "2_2") (pintype "passive"))
      (node (ref "R275") (pin "2") (pinfunction "2_2") (pintype "passive"))
    )
    (net (code "73") (name "Net-(R270-Pad1)") (class "Default")
      (node (ref "R270") (pin "1") (pinfunction "1_1") (pintype "passive"))
      (node (ref "R271") (pin "1") (pinfunction "1_1") (pintype "passive"))
    )
    (net (code "74") (name "Net-(R271-Pad2)") (class "Default")
      (node (ref "R271") (pin "2") (pinfunction "2_2") (pintype "passive"))
      (node (ref "R272") (pin "2") (pinfunction "2_2") (pintype "passive"))
    )
    (net (code "75") (name "Net-(R272-Pad1)") (class "Default")
      (node (ref "R272") (pin "1") (pinfunction "1_1") (pintype "passive"))
      (node (ref "R273") (pin "1") (pinfunction "1_1") (pintype "passive"))
    )
    (net (code "76") (name "Net-(R273-Pad2)") (class "Default")
      (node (ref "R273") (pin "2") (pinfunction "2_2") (pintype "passive"))
      (node (ref "R274") (pin "2") (pinfunction "2_2") (pintype "passive"))
    )
    (net (code "77") (name "Net-(R274-Pad1)") (class "Default")
      (node (ref "R274") (pin "1") (pinfunction "1_1") (pintype "passive"))
      (node (ref "R275") (pin "1") (pinfunction "1_1") (pintype "passive"))
    )
    (net (code "78") (name "Net-(U52-A)") (class "Default")
      (node (ref "JP2") (pin "2") (pinfunction "2_2") (pintype "passive"))
      (node (ref "U52") (pin "1") (pinfunction "A_1") (pintype "passive"))
    )
    (net (code "79") (name "Net-(U52-C)") (class "Default")
      (node (ref "J37") (pin "1") (pinfunction "1_1") (pintype "passive"))
      (node (ref "U52") (pin "4") (pinfunction "C_4") (pintype "passive"))
    )
    (net (code "80") (name "Net-(U52-E)") (class "Default")
      (node (ref "J37") (pin "2") (pinfunction "2_2") (pintype "passive"))
      (node (ref "U52") (pin "3") (pinfunction "E_3") (pintype "passive"))
    )
    (net (code "81") (name "Net-(U52-K)") (class "Default")
      (node (ref "R234") (pin "2") (pinfunction "2_2") (pintype "passive"))
      (node (ref "U52") (pin "2") (pinfunction "K_2") (pintype "passive"))
    )
    (net (code "82") (name "Net-(U53-A)") (class "Default")
      (node (ref "JP3") (pin "2") (pinfunction "2_2") (pintype "passive"))
      (node (ref "U53") (pin "1") (pinfunction "A_1") (pintype "passive"))
    )
    (net (code "83") (name "Net-(U53-C)") (class "Default")
      (node (ref "J37") (pin "3") (pinfunction "3_3") (pintype "passive"))
      (node (ref "U53") (pin "4") (pinfunction "C_4") (pintype "passive"))
    )
    (net (code "84") (name "Net-(U53-E)") (class "Default")
      (node (ref "J37") (pin "4") (pinfunction "4_4") (pintype "passive"))
      (node (ref "U53") (pin "3") (pinfunction "E_3") (pintype "passive"))
    )
    (net (code "85") (name "Net-(U53-K)") (class "Default")
      (node (ref "R241") (pin "2") (pinfunction "2_2") (pintype "passive"))
      (node (ref "U53") (pin "2") (pinfunction "K_2") (pintype "passive"))
    )
    (net (code "86") (name "Net-(U54-A)") (class "Default")
      (node (ref "JP4") (pin "2") (pinfunction "2_2") (pintype "passive"))
      (node (ref "U54") (pin "1") (pinfunction "A_1") (pintype "passive"))
    )
    (net (code "87") (name "Net-(U54-C)") (class "Default")
      (node (ref "J37") (pin "5") (pinfunction "5_5") (pintype "passive"))
      (node (ref "U54") (pin "4") (pinfunction "C_4") (pintype "passive"))
    )
    (net (code "88") (name "Net-(U54-E)") (class "Default")
      (node (ref "J37") (pin "6") (pinfunction "6_6") (pintype "passive"))
      (node (ref "U54") (pin "3") (pinfunction "E_3") (pintype "passive"))
    )
    (net (code "89") (name "Net-(U54-K)") (class "Default")
      (node (ref "R245") (pin "2") (pinfunction "2_2") (pintype "passive"))
      (node (ref "U54") (pin "2") (pinfunction "K_2") (pintype "passive"))
    )
    (net (code "90") (name "Net-(U55-DVDD18)") (class "Default")
      (node (ref "C86") (pin "1") (pintype "passive"))
      (node (ref "C88") (pin "2") (pintype "passive"))
      (node (ref "U55") (pin "42") (pinfunction "VPP_42") (pintype "passive"))
      (node (ref "U55") (pin "43") (pinfunction "DVDD18_43") (pintype "passive"))
    )
    (net (code "91") (name "Net-(U55-OSCI)") (class "Default")
      (node (ref "U55") (pin "20") (pinfunction "OSCI_20") (pintype "passive"))
      (node (ref "X1") (pin "2") (pintype "passive"))
    )
    (net (code "92") (name "Net-(U55-OSCO)") (class "Default")
      (node (ref "U55") (pin "21") (pinfunction "OSCO_21") (pintype "passive"))
      (node (ref "X1") (pin "1") (pintype "passive"))
    )
    (net (code "93") (name "Net-(U55-Vref)") (class "Default")
      (node (ref "C97") (pin "2") (pintype "passive"))
      (node (ref "C98") (pin "2") (pintype "passive"))
      (node (ref "U55") (pin "11") (pinfunction "Vref_11") (pintype "passive"))
    )
    (net (code "94") (name "Net-(U55-~{RST})") (class "Default")
      (node (ref "C85") (pin "2") (pintype "passive"))
      (node (ref "JP1") (pin "1") (pinfunction "1_1") (pintype "passive"))
      (node (ref "R233") (pin "1") (pinfunction "1_1") (pintype "passive"))
      (node (ref "U55") (pin "41") (pinfunction "~{RST}_41") (pintype "passive"))
    )
    (net (code "95") (name "Net-(U56-A)") (class "Default")
      (node (ref "JP5") (pin "2") (pinfunction "2_2") (pintype "passive"))
      (node (ref "U56") (pin "1") (pinfunction "A_1") (pintype "passive"))
    )
    (net (code "96") (name "Net-(U56-C)") (class "Default")
      (node (ref "J37") (pin "7") (pinfunction "7_7") (pintype "passive"))
      (node (ref "U56") (pin "4") (pinfunction "C_4") (pintype "passive"))
    )
    (net (code "97") (name "Net-(U56-E)") (class "Default")
      (node (ref "J37") (pin "8") (pinfunction "8_8") (pintype "passive"))
      (node (ref "U56") (pin "3") (pinfunction "E_3") (pintype "passive"))
    )
    (net (code "98") (name "Net-(U56-K)") (class "Default")
      (node (ref "R249") (pin "2") (pinfunction "2_2") (pintype "passive"))
      (node (ref "U56") (pin "2") (pinfunction "K_2") (pintype "passive"))
    )
    (net (code "99") (name "VCC") (class "Default")
      (node (ref "C87") (pin "2") (pintype "passive"))
      (node (ref "C89") (pin "1") (pintype "passive"))
      (node (ref "P1") (pin "1") (pinfunction "1_1") (pintype "passive"))
      (node (ref "R233") (pin "2") (pinfunction "2_2") (pintype "passive"))
      (node (ref "R237") (pin "1") (pinfunction "1_1") (pintype "passive"))
      (node (ref "U55") (pin "48") (pinfunction "DVDD33_48") (pintype "passive"))
    )
  )
)
